# SaL_GPSTrack.net
KiCad netlist of a schematic drawn in EAGLE
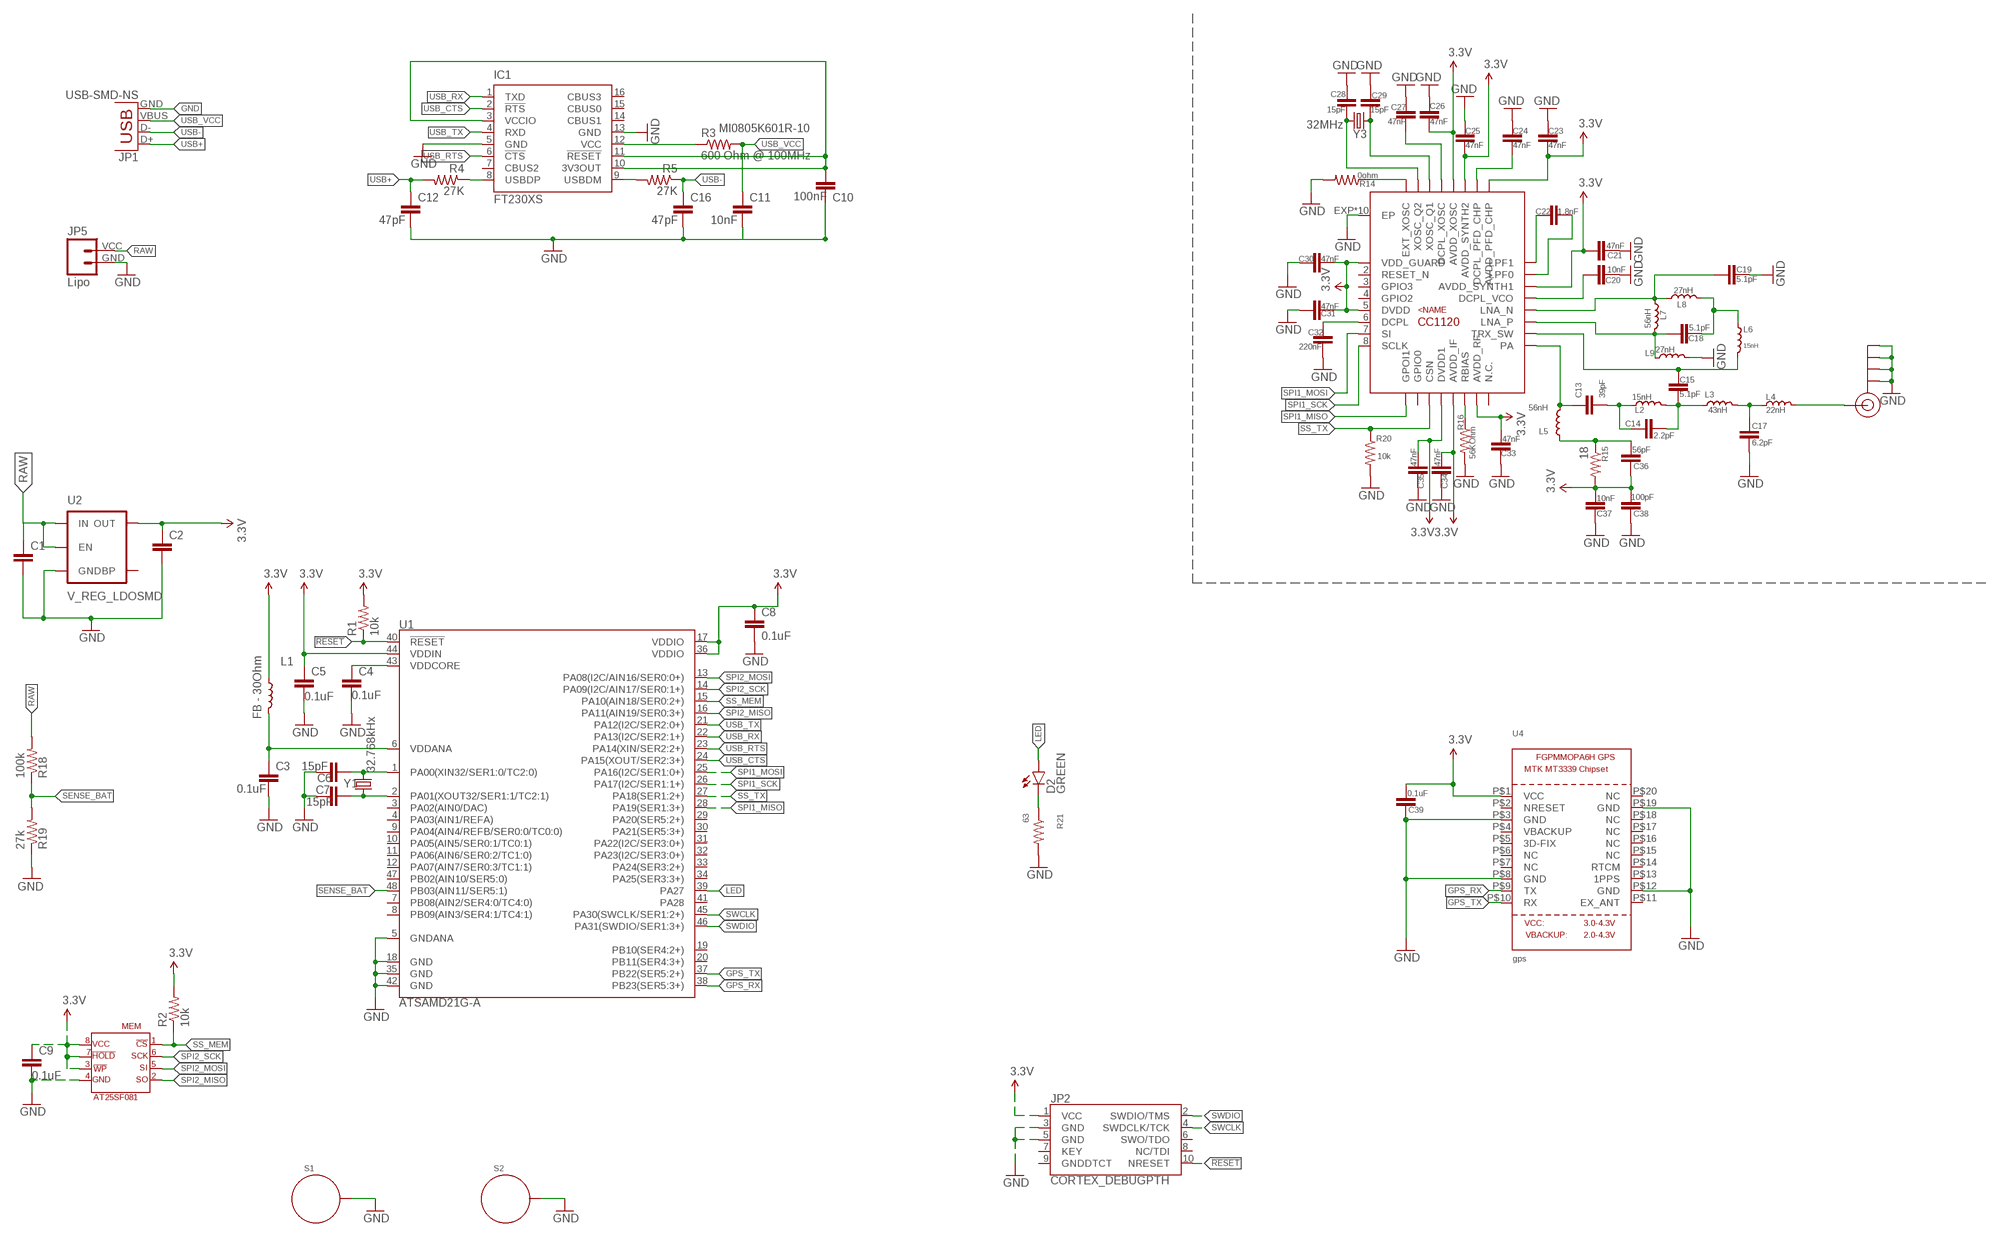
[diagram p0: schematic, sheet 1]

(export (version "E")
  (design (tool "Eeschema 10.0.6"))
  (components
    (comp (ref "C1")
      (value "CAP0603-CAP")
      (footprint "eagle-import:0603-CAP")
      (libsource (lib "eagle-import") (part "CAP0603-CAP"))
    )
    (comp (ref "C2")
      (value "CAP0603-CAP")
      (footprint "eagle-import:0603-CAP")
      (libsource (lib "eagle-import") (part "CAP0603-CAP"))
    )
    (comp (ref "C3")
      (value "0.1uF")
      (footprint "eagle-import:0402-CAP")
      (libsource (lib "eagle-import") (part "SparkFun-Passives_CAP0402-CAP"))
    )
    (comp (ref "C4")
      (value "0.1uF")
      (footprint "eagle-import:0402-CAP")
      (libsource (lib "eagle-import") (part "SparkFun-Passives_CAP0402-CAP"))
    )
    (comp (ref "C5")
      (value "0.1uF")
      (footprint "eagle-import:0402-CAP")
      (libsource (lib "eagle-import") (part "SparkFun-Passives_CAP0402-CAP"))
    )
    (comp (ref "C6")
      (value "15pF")
      (footprint "eagle-import:0402-CAP")
      (libsource (lib "eagle-import") (part "SparkFun-Passives_CAP0402-CAP"))
    )
    (comp (ref "C7")
      (value "15pF")
      (footprint "eagle-import:0402-CAP")
      (libsource (lib "eagle-import") (part "SparkFun-Passives_CAP0402-CAP"))
    )
    (comp (ref "C8")
      (value "0.1uF")
      (footprint "eagle-import:0402-CAP")
      (libsource (lib "eagle-import") (part "SparkFun-Passives_CAP0402-CAP"))
    )
    (comp (ref "C9")
      (value "0.1uF")
      (footprint "eagle-import:0402-CAP")
      (libsource (lib "eagle-import") (part "SparkFun-Passives_CAP0402-CAP"))
    )
    (comp (ref "C10")
      (value "100nF")
      (footprint "eagle-import:0402-CAP")
      (libsource (lib "eagle-import") (part "SparkFun-Passives_CAP0402-CAP"))
    )
    (comp (ref "C11")
      (value "10nF")
      (footprint "eagle-import:0402-CAP")
      (libsource (lib "eagle-import") (part "SparkFun-Passives_CAP0402-CAP"))
    )
    (comp (ref "C12")
      (value "47pF")
      (footprint "eagle-import:0402-CAP")
      (libsource (lib "eagle-import") (part "SparkFun-Passives_CAP0402-CAP"))
    )
    (comp (ref "C13")
      (value "39pF")
      (footprint "eagle-import:0402-CAP")
      (libsource (lib "eagle-import") (part "CAP0402-CAP"))
    )
    (comp (ref "C14")
      (value "2.2pF")
      (footprint "eagle-import:0402-CAP")
      (libsource (lib "eagle-import") (part "CAP0402-CAP"))
    )
    (comp (ref "C15")
      (value "5.1pF")
      (footprint "eagle-import:0402-CAP")
      (libsource (lib "eagle-import") (part "CAP0402-CAP"))
    )
    (comp (ref "C16")
      (value "47pF")
      (footprint "eagle-import:0402-CAP")
      (libsource (lib "eagle-import") (part "SparkFun-Passives_CAP0402-CAP"))
    )
    (comp (ref "C17")
      (value "6.2pF")
      (footprint "eagle-import:0402-CAP")
      (libsource (lib "eagle-import") (part "CAP0402-CAP"))
    )
    (comp (ref "C18")
      (value "5.1pF")
      (footprint "eagle-import:0402-CAP")
      (libsource (lib "eagle-import") (part "CAP0402-CAP"))
    )
    (comp (ref "C19")
      (value "5.1pF")
      (footprint "eagle-import:0402-CAP")
      (libsource (lib "eagle-import") (part "CAP0402-CAP"))
    )
    (comp (ref "C20")
      (value "10nF")
      (footprint "eagle-import:0402-CAP")
      (libsource (lib "eagle-import") (part "CAP0402-CAP"))
    )
    (comp (ref "C21")
      (value "47nF")
      (footprint "eagle-import:0402-CAP")
      (libsource (lib "eagle-import") (part "CAP0402-CAP"))
    )
    (comp (ref "C22")
      (value "1.8nF")
      (footprint "eagle-import:0402-CAP")
      (libsource (lib "eagle-import") (part "CAP0402-CAP"))
    )
    (comp (ref "C23")
      (value "47nF")
      (footprint "eagle-import:0402-CAP")
      (libsource (lib "eagle-import") (part "CAP0402-CAP"))
    )
    (comp (ref "C24")
      (value "47nF")
      (footprint "eagle-import:0402-CAP")
      (libsource (lib "eagle-import") (part "CAP0402-CAP"))
    )
    (comp (ref "C25")
      (value "47nF")
      (footprint "eagle-import:0402-CAP")
      (libsource (lib "eagle-import") (part "CAP0402-CAP"))
    )
    (comp (ref "C26")
      (value "47nF")
      (footprint "eagle-import:0402-CAP")
      (libsource (lib "eagle-import") (part "CAP0402-CAP"))
    )
    (comp (ref "C27")
      (value "47nF")
      (footprint "eagle-import:0402-CAP")
      (libsource (lib "eagle-import") (part "CAP0402-CAP"))
    )
    (comp (ref "C28")
      (value "15pF")
      (footprint "eagle-import:0402-CAP")
      (libsource (lib "eagle-import") (part "CAP0402-CAP"))
    )
    (comp (ref "C29")
      (value "15pF")
      (footprint "eagle-import:0402-CAP")
      (libsource (lib "eagle-import") (part "CAP0402-CAP"))
    )
    (comp (ref "C30")
      (value "47nF")
      (footprint "eagle-import:0402-CAP")
      (libsource (lib "eagle-import") (part "CAP0402-CAP"))
    )
    (comp (ref "C31")
      (value "47nF")
      (footprint "eagle-import:0402-CAP")
      (libsource (lib "eagle-import") (part "CAP0402-CAP"))
    )
    (comp (ref "C32")
      (value "220nF")
      (footprint "eagle-import:0402-CAP")
      (libsource (lib "eagle-import") (part "CAP0402-CAP"))
    )
    (comp (ref "C33")
      (value "47nF")
      (footprint "eagle-import:0402-CAP")
      (libsource (lib "eagle-import") (part "CAP0402-CAP"))
    )
    (comp (ref "C34")
      (value "47nF")
      (footprint "eagle-import:0402-CAP")
      (libsource (lib "eagle-import") (part "CAP0402-CAP"))
    )
    (comp (ref "C35")
      (value "47nF")
      (footprint "eagle-import:0402-CAP")
      (libsource (lib "eagle-import") (part "CAP0402-CAP"))
    )
    (comp (ref "C36")
      (value "56pF")
      (footprint "eagle-import:0402-CAP")
      (libsource (lib "eagle-import") (part "CAP0402-CAP"))
    )
    (comp (ref "C37")
      (value "10nF")
      (footprint "eagle-import:0402-CAP")
      (libsource (lib "eagle-import") (part "CAP0402-CAP"))
    )
    (comp (ref "C38")
      (value "100pF")
      (footprint "eagle-import:0402-CAP")
      (libsource (lib "eagle-import") (part "CAP0402-CAP"))
    )
    (comp (ref "C39")
      (value "0.1uF")
      (footprint "eagle-import:0402-CAP")
      (libsource (lib "eagle-import") (part "CAP0402-CAP"))
    )
    (comp (ref "D2")
      (value "GREEN")
      (footprint "eagle-import:LED-1206")
      (libsource (lib "eagle-import") (part "LED-GREEN1206"))
    )
    (comp (ref "IC1")
      (value "FT230XS")
      (footprint "eagle-import:SSOP16")
      (libsource (lib "eagle-import") (part "FT230XS"))
    )
    (comp (ref "J$1")
      (value "SMA_EDGE")
      (footprint "eagle-import:SMA-EDGE")
      (libsource (lib "eagle-import") (part "SMA_EDGE"))
    )
    (comp (ref "JP1")
      (value "USB-SMD-NS")
      (footprint "eagle-import:USB-MINIB-NOSTOP")
      (libsource (lib "eagle-import") (part "USB-SMD-NS"))
    )
    (comp (ref "JP2")
      (value "CORTEX_DEBUGPTH")
      (footprint "eagle-import:2X5-PTH-1.27MM")
      (libsource (lib "eagle-import") (part "CORTEX_DEBUGPTH"))
    )
    (comp (ref "JP5")
      (value "Lipo")
      (footprint "eagle-import:JST-2-SMD-VERT")
      (libsource (lib "eagle-import") (part "M024UCON-15767"))
    )
    (comp (ref "L1")
      (value "FB - 30Ohm")
      (footprint "eagle-import:0603")
      (libsource (lib "eagle-import") (part "INDUCTOR0603"))
    )
    (comp (ref "L2")
      (value "15nH")
      (footprint "eagle-import:C0402")
      (libsource (lib "eagle-import") (part "INDUCTOR0402"))
    )
    (comp (ref "L3")
      (value "43nH")
      (footprint "eagle-import:C0402")
      (libsource (lib "eagle-import") (part "INDUCTOR0402"))
    )
    (comp (ref "L4")
      (value "22nH")
      (footprint "eagle-import:C0402")
      (libsource (lib "eagle-import") (part "INDUCTOR0402"))
    )
    (comp (ref "L5")
      (value "56nH")
      (footprint "eagle-import:C0402")
      (libsource (lib "eagle-import") (part "INDUCTOR0402"))
    )
    (comp (ref "L6")
      (value "15nH")
      (footprint "eagle-import:C0402")
      (libsource (lib "eagle-import") (part "INDUCTOR0402"))
    )
    (comp (ref "L7")
      (value "56nH")
      (footprint "eagle-import:C0402")
      (libsource (lib "eagle-import") (part "INDUCTOR0402"))
    )
    (comp (ref "L8")
      (value "27nH")
      (footprint "eagle-import:C0402")
      (libsource (lib "eagle-import") (part "INDUCTOR0402"))
    )
    (comp (ref "L9")
      (value "27nH")
      (footprint "eagle-import:C0402")
      (libsource (lib "eagle-import") (part "INDUCTOR0402"))
    )
    (comp (ref "MEM")
      (value "AT25SF081")
      (footprint "eagle-import:AT25SF081")
      (libsource (lib "eagle-import") (part "AT25SF081"))
    )
    (comp (ref "R1")
      (value "10k")
      (footprint "eagle-import:0402-RES")
      (libsource (lib "eagle-import") (part "RESISTOR0402-RES"))
    )
    (comp (ref "R2")
      (value "10k")
      (footprint "eagle-import:0402-RES")
      (libsource (lib "eagle-import") (part "RESISTOR0402-RES"))
    )
    (comp (ref "R3")
      (value "600 Ohm @ 100MHz")
      (footprint "eagle-import:0603-RES")
      (fields (field (name "MI0805K601R-10") "MI0805K601R-10"))
      (libsource (lib "eagle-import") (part "SparkFun-Resistors_RESISTOR0603-RES"))
    )
    (comp (ref "R4")
      (value "27K")
      (footprint "eagle-import:0402-RES")
      (libsource (lib "eagle-import") (part "RESISTOR0402-RES"))
    )
    (comp (ref "R5")
      (value "27K")
      (footprint "eagle-import:0402-RES")
      (libsource (lib "eagle-import") (part "RESISTOR0402-RES"))
    )
    (comp (ref "R14")
      (value "0ohm")
      (footprint "eagle-import:0402-RES")
      (libsource (lib "eagle-import") (part "RESISTOR0402-RES"))
    )
    (comp (ref "R15")
      (value "18")
      (footprint "eagle-import:0402-RES")
      (libsource (lib "eagle-import") (part "RESISTOR0402-RES"))
    )
    (comp (ref "R16")
      (value "56KOhm")
      (footprint "eagle-import:0402-RES")
      (libsource (lib "eagle-import") (part "RESISTOR0402-RES"))
    )
    (comp (ref "R18")
      (value "100k")
      (footprint "eagle-import:0402-RES")
      (libsource (lib "eagle-import") (part "RESISTOR0402-RES"))
    )
    (comp (ref "R19")
      (value "27k")
      (footprint "eagle-import:0402-RES")
      (libsource (lib "eagle-import") (part "RESISTOR0402-RES"))
    )
    (comp (ref "R20")
      (value "10k")
      (footprint "eagle-import:0402-RES")
      (libsource (lib "eagle-import") (part "RESISTOR0402-RES"))
    )
    (comp (ref "R21")
      (value "63")
      (footprint "eagle-import:0402-RES")
      (libsource (lib "eagle-import") (part "RESISTOR0402"))
    )
    (comp (ref "S1")
      (value "STANDOFF_ELECTRICAL")
      (footprint "eagle-import:STANDOFF-ELECTRICAL")
      (libsource (lib "eagle-import") (part "STANDOFF_ELECTRICAL"))
    )
    (comp (ref "S2")
      (value "STANDOFF_ELECTRICAL")
      (footprint "eagle-import:STANDOFF-ELECTRICAL")
      (libsource (lib "eagle-import") (part "STANDOFF_ELECTRICAL"))
    )
    (comp (ref "TX/RX")
      (value "CC1120")
      (footprint "eagle-import:CC1120")
      (libsource (lib "eagle-import") (part "CC1120"))
    )
    (comp (ref "U1")
      (value "ATSAMD21G-A")
      (footprint "eagle-import:TQFP-48")
      (libsource (lib "eagle-import") (part "ATSAMD21G-A"))
    )
    (comp (ref "U2")
      (value "V_REG_LDOSMD")
      (footprint "eagle-import:SOT23-5")
      (libsource (lib "eagle-import") (part "V_REG_LDOSMD"))
    )
    (comp (ref "U4")
      (value "gps")
      (footprint "eagle-import:FGPMMOPA6H")
      (libsource (lib "eagle-import") (part "GPS_FGPMMOPA6H"))
    )
    (comp (ref "Y1")
      (value "32.768kHx")
      (footprint "eagle-import:CRYSTAL-SMD-3.2X1.5MM")
      (libsource (lib "eagle-import") (part "CRYSTAL3.2X1.5MM"))
    )
    (comp (ref "Y3")
      (value "32MHz")
      (footprint "eagle-import:CRYSTAL-SMD-5X3")
      (libsource (lib "eagle-import") (part "CRYSTAL5X3"))
    )
  )
  (nets
    (net (code "1") (name "/~{RESET}") (class "Default")
      (node (ref "JP2") (pin "10") (pinfunction "NRESET_10") (pintype "bidirectional"))
      (node (ref "R1") (pin "1") (pinfunction "1_1") (pintype "passive"))
      (node (ref "U1") (pin "40") (pinfunction "~{RESET}_40") (pintype "bidirectional"))
    )
    (net (code "2") (name "3.3V") (class "Default")
      (node (ref "C2") (pin "1") (pinfunction "1_1") (pintype "passive"))
      (node (ref "C21") (pin "1") (pinfunction "1_1") (pintype "passive"))
      (node (ref "C23") (pin "2") (pinfunction "2_2") (pintype "passive"))
      (node (ref "C25") (pin "2") (pinfunction "2_2") (pintype "passive"))
      (node (ref "C26") (pin "2") (pinfunction "2_2") (pintype "passive"))
      (node (ref "C30") (pin "2") (pinfunction "2_2") (pintype "passive"))
      (node (ref "C31") (pin "2") (pinfunction "2_2") (pintype "passive"))
      (node (ref "C33") (pin "2") (pinfunction "2_2") (pintype "passive"))
      (node (ref "C34") (pin "2") (pinfunction "2_2") (pintype "passive"))
      (node (ref "C35") (pin "2") (pinfunction "2_2") (pintype "passive"))
      (node (ref "C36") (pin "1") (pinfunction "1_1") (pintype "passive"))
      (node (ref "C37") (pin "2") (pinfunction "2_2") (pintype "passive"))
      (node (ref "C38") (pin "2") (pinfunction "2_2") (pintype "passive"))
      (node (ref "C39") (pin "2") (pinfunction "2_2") (pintype "passive"))
      (node (ref "C5") (pin "1") (pinfunction "1_1") (pintype "passive"))
      (node (ref "C8") (pin "1") (pinfunction "1_1") (pintype "passive"))
      (node (ref "C9") (pin "1") (pinfunction "1_1") (pintype "passive"))
      (node (ref "JP2") (pin "1") (pinfunction "VCC_1") (pintype "bidirectional"))
      (node (ref "L1") (pin "1") (pinfunction "1_1") (pintype "passive"))
      (node (ref "MEM") (pin "!HOLD") (pinfunction "~{HOLD}_!HOLD") (pintype "bidirectional"))
      (node (ref "MEM") (pin "!WP") (pinfunction "~{WP}_!WP") (pintype "bidirectional"))
      (node (ref "MEM") (pin "VCC") (pinfunction "VCC_VCC") (pintype "bidirectional"))
      (node (ref "R1") (pin "2") (pinfunction "2_2") (pintype "passive"))
      (node (ref "R15") (pin "2") (pinfunction "2_2") (pintype "passive"))
      (node (ref "R2") (pin "2") (pinfunction "2_2") (pintype "passive"))
      (node (ref "TX/RX") (pin "1") (pinfunction "VDD_GUARD_1") (pintype "bidirectional"))
      (node (ref "TX/RX") (pin "12") (pinfunction "DVDD1_12") (pintype "bidirectional"))
      (node (ref "TX/RX") (pin "13") (pinfunction "AVDD_IF_13") (pintype "bidirectional"))
      (node (ref "TX/RX") (pin "15") (pinfunction "AVDD_RF_15") (pintype "bidirectional"))
      (node (ref "TX/RX") (pin "22") (pinfunction "AVDD_SYNTH1_22") (pintype "bidirectional"))
      (node (ref "TX/RX") (pin "25") (pinfunction "AVDD_PFD_CHP_25") (pintype "bidirectional"))
      (node (ref "TX/RX") (pin "27") (pinfunction "AVDD_SYNTH2_27") (pintype "bidirectional"))
      (node (ref "TX/RX") (pin "28") (pinfunction "AVDD_XOSC_28") (pintype "bidirectional"))
      (node (ref "TX/RX") (pin "5") (pinfunction "DVDD_5") (pintype "bidirectional"))
      (node (ref "U1") (pin "17") (pinfunction "VDDIO_17") (pintype "bidirectional"))
      (node (ref "U1") (pin "36") (pinfunction "VDDIO_36") (pintype "bidirectional"))
      (node (ref "U1") (pin "44") (pinfunction "VDDIN_44") (pintype "bidirectional"))
      (node (ref "U2") (pin "5") (pinfunction "OUT_5") (pintype "passive"))
      (node (ref "U4") (pin "P$1") (pinfunction "VCC_P$1") (pintype "bidirectional"))
    )
    (net (code "3") (name "GND") (class "Default")
      (node (ref "C1") (pin "2") (pinfunction "2_2") (pintype "passive"))
      (node (ref "C10") (pin "2") (pinfunction "2_2") (pintype "passive"))
      (node (ref "C11") (pin "2") (pinfunction "2_2") (pintype "passive"))
      (node (ref "C12") (pin "2") (pinfunction "2_2") (pintype "passive"))
      (node (ref "C16") (pin "2") (pinfunction "2_2") (pintype "passive"))
      (node (ref "C17") (pin "2") (pinfunction "2_2") (pintype "passive"))
      (node (ref "C19") (pin "2") (pinfunction "2_2") (pintype "passive"))
      (node (ref "C2") (pin "2") (pinfunction "2_2") (pintype "passive"))
      (node (ref "C20") (pin "2") (pinfunction "2_2") (pintype "passive"))
      (node (ref "C21") (pin "2") (pinfunction "2_2") (pintype "passive"))
      (node (ref "C23") (pin "1") (pinfunction "1_1") (pintype "passive"))
      (node (ref "C24") (pin "1") (pinfunction "1_1") (pintype "passive"))
      (node (ref "C25") (pin "1") (pinfunction "1_1") (pintype "passive"))
      (node (ref "C26") (pin "1") (pinfunction "1_1") (pintype "passive"))
      (node (ref "C27") (pin "1") (pinfunction "1_1") (pintype "passive"))
      (node (ref "C28") (pin "1") (pinfunction "1_1") (pintype "passive"))
      (node (ref "C29") (pin "1") (pinfunction "1_1") (pintype "passive"))
      (node (ref "C3") (pin "2") (pinfunction "2_2") (pintype "passive"))
      (node (ref "C30") (pin "1") (pinfunction "1_1") (pintype "passive"))
      (node (ref "C31") (pin "1") (pinfunction "1_1") (pintype "passive"))
      (node (ref "C32") (pin "1") (pinfunction "1_1") (pintype "passive"))
      (node (ref "C33") (pin "1") (pinfunction "1_1") (pintype "passive"))
      (node (ref "C34") (pin "1") (pinfunction "1_1") (pintype "passive"))
      (node (ref "C35") (pin "1") (pinfunction "1_1") (pintype "passive"))
      (node (ref "C37") (pin "1") (pinfunction "1_1") (pintype "passive"))
      (node (ref "C38") (pin "1") (pinfunction "1_1") (pintype "passive"))
      (node (ref "C39") (pin "1") (pinfunction "1_1") (pintype "passive"))
      (node (ref "C4") (pin "2") (pinfunction "2_2") (pintype "passive"))
      (node (ref "C5") (pin "2") (pinfunction "2_2") (pintype "passive"))
      (node (ref "C6") (pin "2") (pinfunction "2_2") (pintype "passive"))
      (node (ref "C7") (pin "2") (pinfunction "2_2") (pintype "passive"))
      (node (ref "C8") (pin "2") (pinfunction "2_2") (pintype "passive"))
      (node (ref "C9") (pin "2") (pinfunction "2_2") (pintype "passive"))
      (node (ref "IC1") (pin "13") (pinfunction "GND_13") (pintype "power_in"))
      (node (ref "IC1") (pin "5") (pinfunction "GND_5") (pintype "power_in"))
      (node (ref "J$1") (pin "GND@0") (pinfunction "GND_GND@0") (pintype "bidirectional"))
      (node (ref "J$1") (pin "GND@1") (pinfunction "GND_GND@1") (pintype "bidirectional"))
      (node (ref "J$1") (pin "GND@2") (pinfunction "GND_GND@2") (pintype "bidirectional"))
      (node (ref "J$1") (pin "GND@3") (pinfunction "GND_GND@3") (pintype "bidirectional"))
      (node (ref "JP1") (pin "GND") (pinfunction "GND_GND") (pintype "bidirectional"))
      (node (ref "JP2") (pin "3") (pinfunction "GND_3") (pintype "bidirectional"))
      (node (ref "JP2") (pin "5") (pinfunction "GND_5") (pintype "bidirectional"))
      (node (ref "JP5") (pin "GND") (pinfunction "1_GND") (pintype "passive"))
      (node (ref "L9") (pin "2") (pinfunction "2_2") (pintype "passive"))
      (node (ref "MEM") (pin "GND") (pinfunction "GND_GND") (pintype "bidirectional"))
      (node (ref "R14") (pin "2") (pinfunction "2_2") (pintype "passive"))
      (node (ref "R16") (pin "2") (pinfunction "2_2") (pintype "passive"))
      (node (ref "R19") (pin "1") (pinfunction "1_1") (pintype "passive"))
      (node (ref "R20") (pin "2") (pinfunction "2_2") (pintype "passive"))
      (node (ref "R21") (pin "2") (pinfunction "2_2") (pintype "passive"))
      (node (ref "S1") (pin "P1") (pinfunction "P$1_P1") (pintype "bidirectional"))
      (node (ref "S2") (pin "P1") (pinfunction "P$1_P1") (pintype "bidirectional"))
      (node (ref "TX/RX") (pin "EXP") (pinfunction "EP_EXP") (pintype "bidirectional"))
      (node (ref "TX/RX") (pin "EXP@1") (pinfunction "EP_EXP@1") (pintype "bidirectional"))
      (node (ref "TX/RX") (pin "EXP@2") (pinfunction "EP_EXP@2") (pintype "bidirectional"))
      (node (ref "TX/RX") (pin "EXP@3") (pinfunction "EP_EXP@3") (pintype "bidirectional"))
      (node (ref "TX/RX") (pin "EXP@4") (pinfunction "EP_EXP@4") (pintype "bidirectional"))
      (node (ref "TX/RX") (pin "EXP@5") (pinfunction "EP_EXP@5") (pintype "bidirectional"))
      (node (ref "TX/RX") (pin "EXP@6") (pinfunction "EP_EXP@6") (pintype "bidirectional"))
      (node (ref "TX/RX") (pin "EXP@7") (pinfunction "EP_EXP@7") (pintype "bidirectional"))
      (node (ref "TX/RX") (pin "EXP@8") (pinfunction "EP_EXP@8") (pintype "bidirectional"))
      (node (ref "TX/RX") (pin "EXP@9") (pinfunction "EP_EXP@9") (pintype "bidirectional"))
      (node (ref "U1") (pin "18") (pinfunction "GND_18") (pintype "bidirectional"))
      (node (ref "U1") (pin "35") (pinfunction "GND_35") (pintype "bidirectional"))
      (node (ref "U1") (pin "42") (pinfunction "GND_42") (pintype "bidirectional"))
      (node (ref "U1") (pin "5") (pinfunction "GNDANA_5") (pintype "bidirectional"))
      (node (ref "U2") (pin "2") (pinfunction "GND_2") (pintype "input"))
      (node (ref "U4") (pin "P$12") (pinfunction "GND_P$12") (pintype "bidirectional"))
      (node (ref "U4") (pin "P$19") (pinfunction "GND_P$19") (pintype "bidirectional"))
      (node (ref "U4") (pin "P$3") (pinfunction "GND_P$3") (pintype "bidirectional"))
      (node (ref "U4") (pin "P$8") (pinfunction "GND_P$8") (pintype "bidirectional"))
    )
    (net (code "4") (name "GPS_RX") (class "Default")
      (node (ref "U1") (pin "38") (pinfunction "PB23(SER5:3+)_38") (pintype "bidirectional"))
      (node (ref "U4") (pin "P$9") (pinfunction "TX_P$9") (pintype "bidirectional"))
    )
    (net (code "5") (name "GPS_TX") (class "Default")
      (node (ref "U1") (pin "37") (pinfunction "PB22(SER5:2+)_37") (pintype "bidirectional"))
      (node (ref "U4") (pin "P$10") (pinfunction "RX_P$10") (pintype "bidirectional"))
    )
    (net (code "6") (name "LED") (class "Default")
      (node (ref "D2") (pin "A") (pinfunction "A_A") (pintype "passive"))
      (node (ref "U1") (pin "39") (pinfunction "PA27_39") (pintype "bidirectional"))
    )
    (net (code "7") (name "Net-(C13-Pad2)") (class "Default")
      (node (ref "C13") (pin "2") (pinfunction "2_2") (pintype "passive"))
      (node (ref "C14") (pin "1") (pinfunction "1_1") (pintype "passive"))
      (node (ref "L2") (pin "1") (pinfunction "1_1") (pintype "passive"))
    )
    (net (code "8") (name "Net-(C14-Pad2)") (class "Default")
      (node (ref "C14") (pin "2") (pinfunction "2_2") (pintype "passive"))
      (node (ref "C15") (pin "1") (pinfunction "1_1") (pintype "passive"))
      (node (ref "L2") (pin "2") (pinfunction "2_2") (pintype "passive"))
      (node (ref "L3") (pin "1") (pinfunction "1_1") (pintype "passive"))
    )
    (net (code "9") (name "Net-(C17-Pad1)") (class "Default")
      (node (ref "C17") (pin "1") (pinfunction "1_1") (pintype "passive"))
      (node (ref "L3") (pin "2") (pinfunction "2_2") (pintype "passive"))
      (node (ref "L4") (pin "1") (pinfunction "1_1") (pintype "passive"))
    )
    (net (code "10") (name "Net-(C18-Pad2)") (class "Default")
      (node (ref "C18") (pin "2") (pinfunction "2_2") (pintype "passive"))
      (node (ref "L6") (pin "1") (pinfunction "1_1") (pintype "passive"))
      (node (ref "L8") (pin "2") (pinfunction "2_2") (pintype "passive"))
    )
    (net (code "11") (name "Net-(C36-Pad2)") (class "Default")
      (node (ref "C36") (pin "2") (pinfunction "2_2") (pintype "passive"))
      (node (ref "L5") (pin "1") (pinfunction "1_1") (pintype "passive"))
      (node (ref "R15") (pin "1") (pinfunction "1_1") (pintype "passive"))
    )
    (net (code "12") (name "Net-(D2-PadC)") (class "Default")
      (node (ref "D2") (pin "C") (pinfunction "C_C") (pintype "passive"))
      (node (ref "R21") (pin "1") (pinfunction "1_1") (pintype "passive"))
    )
    (net (code "13") (name "Net-(IC1-3V3OUT)") (class "Default")
      (node (ref "C10") (pin "1") (pinfunction "1_1") (pintype "passive"))
      (node (ref "IC1") (pin "10") (pinfunction "3V3OUT_10") (pintype "output"))
      (node (ref "IC1") (pin "11") (pinfunction "~{RESET}_11") (pintype "input"))
      (node (ref "IC1") (pin "3") (pinfunction "VCCIO_3") (pintype "power_in"))
    )
    (net (code "14") (name "Net-(IC1-USBDM)") (class "Default")
      (node (ref "IC1") (pin "9") (pinfunction "USBDM_9") (pintype "input"))
      (node (ref "R5") (pin "2") (pinfunction "2_2") (pintype "passive"))
    )
    (net (code "15") (name "Net-(IC1-USBDP)") (class "Default")
      (node (ref "IC1") (pin "8") (pinfunction "USBDP_8") (pintype "input"))
      (node (ref "R4") (pin "1") (pinfunction "1_1") (pintype "passive"))
    )
    (net (code "16") (name "Net-(IC1-VCC)") (class "Default")
      (node (ref "IC1") (pin "12") (pinfunction "VCC_12") (pintype "power_in"))
      (node (ref "R3") (pin "1") (pinfunction "1_1") (pintype "passive"))
    )
    (net (code "17") (name "Net-(J$1-SIGNAL)") (class "Default")
      (node (ref "J$1") (pin "SIG") (pinfunction "SIGNAL_SIG") (pintype "bidirectional"))
      (node (ref "L4") (pin "2") (pinfunction "2_2") (pintype "passive"))
    )
    (net (code "18") (name "Net-(TX/RX-DCPL)") (class "Default")
      (node (ref "C32") (pin "2") (pinfunction "2_2") (pintype "passive"))
      (node (ref "TX/RX") (pin "6") (pinfunction "DCPL_6") (pintype "bidirectional"))
    )
    (net (code "19") (name "Net-(TX/RX-DCPL_PFD_CHP)") (class "Default")
      (node (ref "C24") (pin "2") (pinfunction "2_2") (pintype "passive"))
      (node (ref "TX/RX") (pin "26") (pinfunction "DCPL_PFD_CHP_26") (pintype "bidirectional"))
    )
    (net (code "20") (name "Net-(TX/RX-DCPL_VCO)") (class "Default")
      (node (ref "C20") (pin "1") (pinfunction "1_1") (pintype "passive"))
      (node (ref "TX/RX") (pin "21") (pinfunction "DCPL_VCO_21") (pintype "bidirectional"))
    )
    (net (code "21") (name "Net-(TX/RX-DCPL_XOSC)") (class "Default")
      (node (ref "C27") (pin "2") (pinfunction "2_2") (pintype "passive"))
      (node (ref "TX/RX") (pin "29") (pinfunction "DCPL_XOSC_29") (pintype "bidirectional"))
    )
    (net (code "22") (name "Net-(TX/RX-EXT_XOSC)") (class "Default")
      (node (ref "R14") (pin "1") (pinfunction "1_1") (pintype "passive"))
      (node (ref "TX/RX") (pin "32") (pinfunction "EXT_XOSC_32") (pintype "bidirectional"))
    )
    (net (code "23") (name "Net-(TX/RX-LNA_N)") (class "Default")
      (node (ref "C19") (pin "1") (pinfunction "1_1") (pintype "passive"))
      (node (ref "L7") (pin "1") (pinfunction "1_1") (pintype "passive"))
      (node (ref "L8") (pin "1") (pinfunction "1_1") (pintype "passive"))
      (node (ref "TX/RX") (pin "20") (pinfunction "LNA_N_20") (pintype "bidirectional"))
    )
    (net (code "24") (name "Net-(TX/RX-LNA_P)") (class "Default")
      (node (ref "C18") (pin "1") (pinfunction "1_1") (pintype "passive"))
      (node (ref "L7") (pin "2") (pinfunction "2_2") (pintype "passive"))
      (node (ref "L9") (pin "1") (pinfunction "1_1") (pintype "passive"))
      (node (ref "TX/RX") (pin "19") (pinfunction "LNA_P_19") (pintype "bidirectional"))
    )
    (net (code "25") (name "Net-(TX/RX-LPF0)") (class "Default")
      (node (ref "C22") (pin "2") (pinfunction "2_2") (pintype "passive"))
      (node (ref "TX/RX") (pin "23") (pinfunction "LPF0_23") (pintype "bidirectional"))
    )
    (net (code "26") (name "Net-(TX/RX-LPF1)") (class "Default")
      (node (ref "C22") (pin "1") (pinfunction "1_1") (pintype "passive"))
      (node (ref "TX/RX") (pin "24") (pinfunction "LPF1_24") (pintype "bidirectional"))
    )
    (net (code "27") (name "Net-(TX/RX-PA)") (class "Default")
      (node (ref "C13") (pin "1") (pinfunction "1_1") (pintype "passive"))
      (node (ref "L5") (pin "2") (pinfunction "2_2") (pintype "passive"))
      (node (ref "TX/RX") (pin "17") (pinfunction "PA_17") (pintype "bidirectional"))
    )
    (net (code "28") (name "Net-(TX/RX-RBIAS)") (class "Default")
      (node (ref "R16") (pin "1") (pinfunction "1_1") (pintype "passive"))
      (node (ref "TX/RX") (pin "14") (pinfunction "RBIAS_14") (pintype "bidirectional"))
    )
    (net (code "29") (name "Net-(TX/RX-TRX_SW)") (class "Default")
      (node (ref "C15") (pin "2") (pinfunction "2_2") (pintype "passive"))
      (node (ref "L6") (pin "2") (pinfunction "2_2") (pintype "passive"))
      (node (ref "TX/RX") (pin "18") (pinfunction "TRX_SW_18") (pintype "bidirectional"))
    )
    (net (code "30") (name "Net-(TX/RX-XOSC_Q1)") (class "Default")
      (node (ref "C29") (pin "2") (pinfunction "2_2") (pintype "passive"))
      (node (ref "TX/RX") (pin "30") (pinfunction "XOSC_Q1_30") (pintype "bidirectional"))
      (node (ref "Y3") (pin "3") (pinfunction "2_3") (pintype "passive"))
    )
    (net (code "31") (name "Net-(TX/RX-XOSC_Q2)") (class "Default")
      (node (ref "C28") (pin "2") (pinfunction "2_2") (pintype "passive"))
      (node (ref "TX/RX") (pin "31") (pinfunction "XOSC_Q2_31") (pintype "bidirectional"))
      (node (ref "Y3") (pin "1") (pinfunction "1_1") (pintype "passive"))
    )
    (net (code "32") (name "Net-(U1-PA00(XIN32{slash}SER1:0{slash}TC2:0))") (class "Default")
      (node (ref "C6") (pin "1") (pinfunction "1_1") (pintype "passive"))
      (node (ref "U1") (pin "1") (pinfunction "PA00(XIN32/SER1:0/TC2:0)_1") (pintype "bidirectional"))
      (node (ref "Y1") (pin "P$2") (pinfunction "2_P$2") (pintype "passive"))
    )
    (net (code "33") (name "Net-(U1-PA01(XOUT32{slash}SER1:1{slash}TC2:1))") (class "Default")
      (node (ref "C7") (pin "1") (pinfunction "1_1") (pintype "passive"))
      (node (ref "U1") (pin "2") (pinfunction "PA01(XOUT32/SER1:1/TC2:1)_2") (pintype "bidirectional"))
      (node (ref "Y1") (pin "P$1") (pinfunction "1_P$1") (pintype "passive"))
    )
    (net (code "34") (name "Net-(U1-VDDANA)") (class "Default")
      (node (ref "C3") (pin "1") (pinfunction "1_1") (pintype "passive"))
      (node (ref "L1") (pin "2") (pinfunction "2_2") (pintype "passive"))
      (node (ref "U1") (pin "6") (pinfunction "VDDANA_6") (pintype "bidirectional"))
    )
    (net (code "35") (name "Net-(U1-VDDCORE)") (class "Default")
      (node (ref "C4") (pin "1") (pinfunction "1_1") (pintype "passive"))
      (node (ref "U1") (pin "43") (pinfunction "VDDCORE_43") (pintype "bidirectional"))
    )
    (net (code "36") (name "RAW") (class "Default")
      (node (ref "C1") (pin "1") (pinfunction "1_1") (pintype "passive"))
      (node (ref "JP5") (pin "VCC") (pinfunction "2_VCC") (pintype "passive"))
      (node (ref "R18") (pin "2") (pinfunction "2_2") (pintype "passive"))
      (node (ref "U2") (pin "1") (pinfunction "IN_1") (pintype "input"))
      (node (ref "U2") (pin "3") (pinfunction "EN_3") (pintype "input"))
    )
    (net (code "37") (name "SENSE_BAT") (class "Default")
      (node (ref "R18") (pin "1") (pinfunction "1_1") (pintype "passive"))
      (node (ref "R19") (pin "2") (pinfunction "2_2") (pintype "passive"))
      (node (ref "U1") (pin "48") (pinfunction "PB03(AIN11/SER5:1)_48") (pintype "bidirectional"))
    )
    (net (code "38") (name "SPI1_MISO") (class "Default")
      (node (ref "TX/RX") (pin "9") (pinfunction "GPOI1_9") (pintype "bidirectional"))
      (node (ref "U1") (pin "28") (pinfunction "PA19(SER1:3+)_28") (pintype "bidirectional"))
    )
    (net (code "39") (name "SPI1_MOSI") (class "Default")
      (node (ref "TX/RX") (pin "7") (pinfunction "SI_7") (pintype "bidirectional"))
      (node (ref "U1") (pin "25") (pinfunction "PA16(I2C/SER1:0+)_25") (pintype "bidirectional"))
    )
    (net (code "40") (name "SPI1_SCK") (class "Default")
      (node (ref "TX/RX") (pin "8") (pinfunction "SCLK_8") (pintype "bidirectional"))
      (node (ref "U1") (pin "26") (pinfunction "PA17(I2C/SER1:1+)_26") (pintype "bidirectional"))
    )
    (net (code "41") (name "SPI2_MISO") (class "Default")
      (node (ref "MEM") (pin "SO") (pinfunction "SO_SO") (pintype "bidirectional"))
      (node (ref "U1") (pin "16") (pinfunction "PA11(AIN19/SER0:3+)_16") (pintype "bidirectional"))
    )
    (net (code "42") (name "SPI2_MOSI") (class "Default")
      (node (ref "MEM") (pin "SI") (pinfunction "SI_SI") (pintype "bidirectional"))
      (node (ref "U1") (pin "13") (pinfunction "PA08(I2C/AIN16/SER0:0+)_13") (pintype "bidirectional"))
    )
    (net (code "43") (name "SPI2_SCK") (class "Default")
      (node (ref "MEM") (pin "SCK") (pinfunction "SCK_SCK") (pintype "bidirectional"))
      (node (ref "U1") (pin "14") (pinfunction "PA09(I2C/AIN17/SER0:1+)_14") (pintype "bidirectional"))
    )
    (net (code "44") (name "SS_MEM") (class "Default")
      (node (ref "MEM") (pin "!CS") (pinfunction "~{CS}_!CS") (pintype "bidirectional"))
      (node (ref "R2") (pin "1") (pinfunction "1_1") (pintype "passive"))
      (node (ref "U1") (pin "15") (pinfunction "PA10(AIN18/SER0:2+)_15") (pintype "bidirectional"))
    )
    (net (code "45") (name "SS_TX") (class "Default")
      (node (ref "R20") (pin "1") (pinfunction "1_1") (pintype "passive"))
      (node (ref "TX/RX") (pin "11") (pinfunction "CSN_11") (pintype "bidirectional"))
      (node (ref "U1") (pin "27") (pinfunction "PA18(SER1:2+)_27") (pintype "bidirectional"))
    )
    (net (code "46") (name "SWCLK") (class "Default")
      (node (ref "JP2") (pin "4") (pinfunction "SWDCLK/TCK_4") (pintype "bidirectional"))
      (node (ref "U1") (pin "45") (pinfunction "PA30(SWCLK/SER1:2+)_45") (pintype "bidirectional"))
    )
    (net (code "47") (name "SWDIO") (class "Default")
      (node (ref "JP2") (pin "2") (pinfunction "SWDIO/TMS_2") (pintype "bidirectional"))
      (node (ref "U1") (pin "46") (pinfunction "PA31(SWDIO/SER1:3+)_46") (pintype "bidirectional"))
    )
    (net (code "48") (name "USB+") (class "Default")
      (node (ref "C12") (pin "1") (pinfunction "1_1") (pintype "passive"))
      (node (ref "JP1") (pin "D+") (pinfunction "D+_D+") (pintype "bidirectional"))
      (node (ref "R4") (pin "2") (pinfunction "2_2") (pintype "passive"))
    )
    (net (code "49") (name "USB-") (class "Default")
      (node (ref "C16") (pin "1") (pinfunction "1_1") (pintype "passive"))
      (node (ref "JP1") (pin "D-") (pinfunction "D-_D-") (pintype "bidirectional"))
      (node (ref "R5") (pin "1") (pinfunction "1_1") (pintype "passive"))
    )
    (net (code "50") (name "USB_CTS") (class "Default")
      (node (ref "IC1") (pin "2") (pinfunction "~{RTS}_2") (pintype "output"))
      (node (ref "U1") (pin "24") (pinfunction "PA15(XOUT/SER2:3+)_24") (pintype "bidirectional"))
    )
    (net (code "51") (name "USB_RTS") (class "Default")
      (node (ref "IC1") (pin "6") (pinfunction "~{CTS}_6") (pintype "input"))
      (node (ref "U1") (pin "23") (pinfunction "PA14(XIN/SER2:2+)_23") (pintype "bidirectional"))
    )
    (net (code "52") (name "USB_RX") (class "Default")
      (node (ref "IC1") (pin "1") (pinfunction "TXD_1") (pintype "output"))
      (node (ref "U1") (pin "22") (pinfunction "PA13(I2C/SER2:1+)_22") (pintype "bidirectional"))
    )
    (net (code "53") (name "USB_TX") (class "Default")
      (node (ref "IC1") (pin "4") (pinfunction "RXD_4") (pintype "input"))
      (node (ref "U1") (pin "21") (pinfunction "PA12(I2C/SER2:0+)_21") (pintype "bidirectional"))
    )
    (net (code "54") (name "USB_VCC") (class "Default")
      (node (ref "C11") (pin "1") (pinfunction "1_1") (pintype "passive"))
      (node (ref "JP1") (pin "VBUS") (pinfunction "VBUS_VBUS") (pintype "bidirectional"))
      (node (ref "R3") (pin "2") (pinfunction "2_2") (pintype "passive"))
    )
    (net (code "55") (name "unconnected-(IC1-CBUS0-Pad15)") (class "Default")
      (node (ref "IC1") (pin "15") (pinfunction "CBUS0_15") (pintype "bidirectional"))
    )
    (net (code "56") (name "unconnected-(IC1-CBUS1-Pad14)") (class "Default")
      (node (ref "IC1") (pin "14") (pinfunction "CBUS1_14") (pintype "bidirectional"))
    )
    (net (code "57") (name "unconnected-(IC1-CBUS2-Pad7)") (class "Default")
      (node (ref "IC1") (pin "7") (pinfunction "CBUS2_7") (pintype "bidirectional"))
    )
    (net (code "58") (name "unconnected-(IC1-CBUS3-Pad16)") (class "Default")
      (node (ref "IC1") (pin "16") (pinfunction "CBUS3_16") (pintype "bidirectional"))
    )
    (net (code "59") (name "unconnected-(JP2-GNDDTCT-Pad9)") (class "Default")
      (node (ref "JP2") (pin "9") (pinfunction "GNDDTCT_9") (pintype "bidirectional"))
    )
    (net (code "60") (name "unconnected-(JP2-KEY-Pad7)") (class "Default")
      (node (ref "JP2") (pin "7") (pinfunction "KEY_7") (pintype "bidirectional"))
    )
    (net (code "61") (name "unconnected-(JP2-NC{slash}TDI-Pad8)") (class "Default")
      (node (ref "JP2") (pin "8") (pinfunction "NC/TDI_8") (pintype "bidirectional"))
    )
    (net (code "62") (name "unconnected-(JP2-SWO{slash}TDO-Pad6)") (class "Default")
      (node (ref "JP2") (pin "6") (pinfunction "SWO/TDO_6") (pintype "bidirectional"))
    )
    (net (code "63") (name "unconnected-(TX/RX-GPIO0-Pad10)") (class "Default")
      (node (ref "TX/RX") (pin "10") (pinfunction "GPIO0_10") (pintype "bidirectional"))
    )
    (net (code "64") (name "unconnected-(TX/RX-GPIO2-Pad4)") (class "Default")
      (node (ref "TX/RX") (pin "4") (pinfunction "GPIO2_4") (pintype "bidirectional"))
    )
    (net (code "65") (name "unconnected-(TX/RX-GPIO3-Pad3)") (class "Default")
      (node (ref "TX/RX") (pin "3") (pinfunction "GPIO3_3") (pintype "bidirectional"))
    )
    (net (code "66") (name "unconnected-(TX/RX-N.C.-Pad16)") (class "Default")
      (node (ref "TX/RX") (pin "16") (pinfunction "N.C._16") (pintype "bidirectional"))
    )
    (net (code "67") (name "unconnected-(TX/RX-RESET_N-Pad2)") (class "Default")
      (node (ref "TX/RX") (pin "2") (pinfunction "RESET_N_2") (pintype "bidirectional"))
    )
    (net (code "68") (name "unconnected-(U1-PA02(AIN0{slash}DAC)-Pad3)") (class "Default")
      (node (ref "U1") (pin "3") (pinfunction "PA02(AIN0/DAC)_3") (pintype "bidirectional"))
    )
    (net (code "69") (name "unconnected-(U1-PA03(AIN1{slash}REFA)-Pad4)") (class "Default")
      (node (ref "U1") (pin "4") (pinfunction "PA03(AIN1/REFA)_4") (pintype "bidirectional"))
    )
    (net (code "70") (name "unconnected-(U1-PA04(AIN4{slash}REFB{slash}SER0:0{slash}TC0:0)-Pad9)") (class "Default")
      (node (ref "U1") (pin "9") (pinfunction "PA04(AIN4/REFB/SER0:0/TC0:0)_9") (pintype "bidirectional"))
    )
    (net (code "71") (name "unconnected-(U1-PA05(AIN5{slash}SER0:1{slash}TC0:1)-Pad10)") (class "Default")
      (node (ref "U1") (pin "10") (pinfunction "PA05(AIN5/SER0:1/TC0:1)_10") (pintype "bidirectional"))
    )
    (net (code "72") (name "unconnected-(U1-PA06(AIN6{slash}SER0:2{slash}TC1:0)-Pad11)") (class "Default")
      (node (ref "U1") (pin "11") (pinfunction "PA06(AIN6/SER0:2/TC1:0)_11") (pintype "bidirectional"))
    )
    (net (code "73") (name "unconnected-(U1-PA07(AIN7{slash}SER0:3{slash}TC1:1)-Pad12)") (class "Default")
      (node (ref "U1") (pin "12") (pinfunction "PA07(AIN7/SER0:3/TC1:1)_12") (pintype "bidirectional"))
    )
    (net (code "74") (name "unconnected-(U1-PA20(SER5:2+)-Pad29)") (class "Default")
      (node (ref "U1") (pin "29") (pinfunction "PA20(SER5:2+)_29") (pintype "bidirectional"))
    )
    (net (code "75") (name "unconnected-(U1-PA21(SER5:3+)-Pad30)") (class "Default")
      (node (ref "U1") (pin "30") (pinfunction "PA21(SER5:3+)_30") (pintype "bidirectional"))
    )
    (net (code "76") (name "unconnected-(U1-PA22(I2C{slash}SER3:0+)-Pad31)") (class "Default")
      (node (ref "U1") (pin "31") (pinfunction "PA22(I2C/SER3:0+)_31") (pintype "bidirectional"))
    )
    (net (code "77") (name "unconnected-(U1-PA23(I2C{slash}SER3:0+)-Pad32)") (class "Default")
      (node (ref "U1") (pin "32") (pinfunction "PA23(I2C/SER3:0+)_32") (pintype "bidirectional"))
    )
    (net (code "78") (name "unconnected-(U1-PA24(SER3:2+)-Pad33)") (class "Default")
      (node (ref "U1") (pin "33") (pinfunction "PA24(SER3:2+)_33") (pintype "bidirectional"))
    )
    (net (code "79") (name "unconnected-(U1-PA25(SER3:3+)-Pad34)") (class "Default")
      (node (ref "U1") (pin "34") (pinfunction "PA25(SER3:3+)_34") (pintype "bidirectional"))
    )
    (net (code "80") (name "unconnected-(U1-PA28-Pad41)") (class "Default")
      (node (ref "U1") (pin "41") (pinfunction "PA28_41") (pintype "bidirectional"))
    )
    (net (code "81") (name "unconnected-(U1-PB02(AIN10{slash}SER5:0)-Pad47)") (class "Default")
      (node (ref "U1") (pin "47") (pinfunction "PB02(AIN10/SER5:0)_47") (pintype "bidirectional"))
    )
    (net (code "82") (name "unconnected-(U1-PB08(AIN2{slash}SER4:0{slash}TC4:0)-Pad7)") (class "Default")
      (node (ref "U1") (pin "7") (pinfunction "PB08(AIN2/SER4:0/TC4:0)_7") (pintype "bidirectional"))
    )
    (net (code "83") (name "unconnected-(U1-PB09(AIN3{slash}SER4:1{slash}TC4:1)-Pad8)") (class "Default")
      (node (ref "U1") (pin "8") (pinfunction "PB09(AIN3/SER4:1/TC4:1)_8") (pintype "bidirectional"))
    )
    (net (code "84") (name "unconnected-(U1-PB10(SER4:2+)-Pad19)") (class "Default")
      (node (ref "U1") (pin "19") (pinfunction "PB10(SER4:2+)_19") (pintype "bidirectional"))
    )
    (net (code "85") (name "unconnected-(U1-PB11(SER4:3+)-Pad20)") (class "Default")
      (node (ref "U1") (pin "20") (pinfunction "PB11(SER4:3+)_20") (pintype "bidirectional"))
    )
    (net (code "86") (name "unconnected-(U2-BP-Pad4)") (class "Default")
      (node (ref "U2") (pin "4") (pinfunction "BP_4") (pintype "input"))
    )
    (net (code "87") (name "unconnected-(U4-1PPS-PadP$13)") (class "Default")
      (node (ref "U4") (pin "P$13") (pinfunction "1PPS_P$13") (pintype "bidirectional"))
    )
    (net (code "88") (name "unconnected-(U4-3D-FIX-PadP$5)") (class "Default")
      (node (ref "U4") (pin "P$5") (pinfunction "3D-FIX_P$5") (pintype "bidirectional"))
    )
    (net (code "89") (name "unconnected-(U4-EX_ANT-PadP$11)") (class "Default")
      (node (ref "U4") (pin "P$11") (pinfunction "EX_ANT_P$11") (pintype "bidirectional"))
    )
    (net (code "90") (name "unconnected-(U4-NC-PadP$6)") (class "Default")
      (node (ref "U4") (pin "P$6") (pinfunction "NC_P$6") (pintype "bidirectional"))
    )
    (net (code "91") (name "unconnected-(U4-NC-PadP$7)") (class "Default")
      (node (ref "U4") (pin "P$7") (pinfunction "NC_P$7") (pintype "bidirectional"))
    )
    (net (code "92") (name "unconnected-(U4-NC-PadP$15)") (class "Default")
      (node (ref "U4") (pin "P$15") (pinfunction "NC_P$15") (pintype "bidirectional"))
    )
    (net (code "93") (name "unconnected-(U4-NC-PadP$16)") (class "Default")
      (node (ref "U4") (pin "P$16") (pinfunction "NC_P$16") (pintype "bidirectional"))
    )
    (net (code "94") (name "unconnected-(U4-NC-PadP$17)") (class "Default")
      (node (ref "U4") (pin "P$17") (pinfunction "NC_P$17") (pintype "bidirectional"))
    )
    (net (code "95") (name "unconnected-(U4-NC-PadP$18)") (class "Default")
      (node (ref "U4") (pin "P$18") (pinfunction "NC_P$18") (pintype "bidirectional"))
    )
    (net (code "96") (name "unconnected-(U4-NC-PadP$20)") (class "Default")
      (node (ref "U4") (pin "P$20") (pinfunction "NC_P$20") (pintype "bidirectional"))
    )
    (net (code "97") (name "unconnected-(U4-NRESET-PadP$2)") (class "Default")
      (node (ref "U4") (pin "P$2") (pinfunction "NRESET_P$2") (pintype "bidirectional"))
    )
    (net (code "98") (name "unconnected-(U4-RTCM-PadP$14)") (class "Default")
      (node (ref "U4") (pin "P$14") (pinfunction "RTCM_P$14") (pintype "bidirectional"))
    )
    (net (code "99") (name "unconnected-(U4-VBACKUP-PadP$4)") (class "Default")
      (node (ref "U4") (pin "P$4") (pinfunction "VBACKUP_P$4") (pintype "bidirectional"))
    )
  )
)
